# Sheet_MEZ.net
KiCad netlist of a schematic drawn in Altium Designer
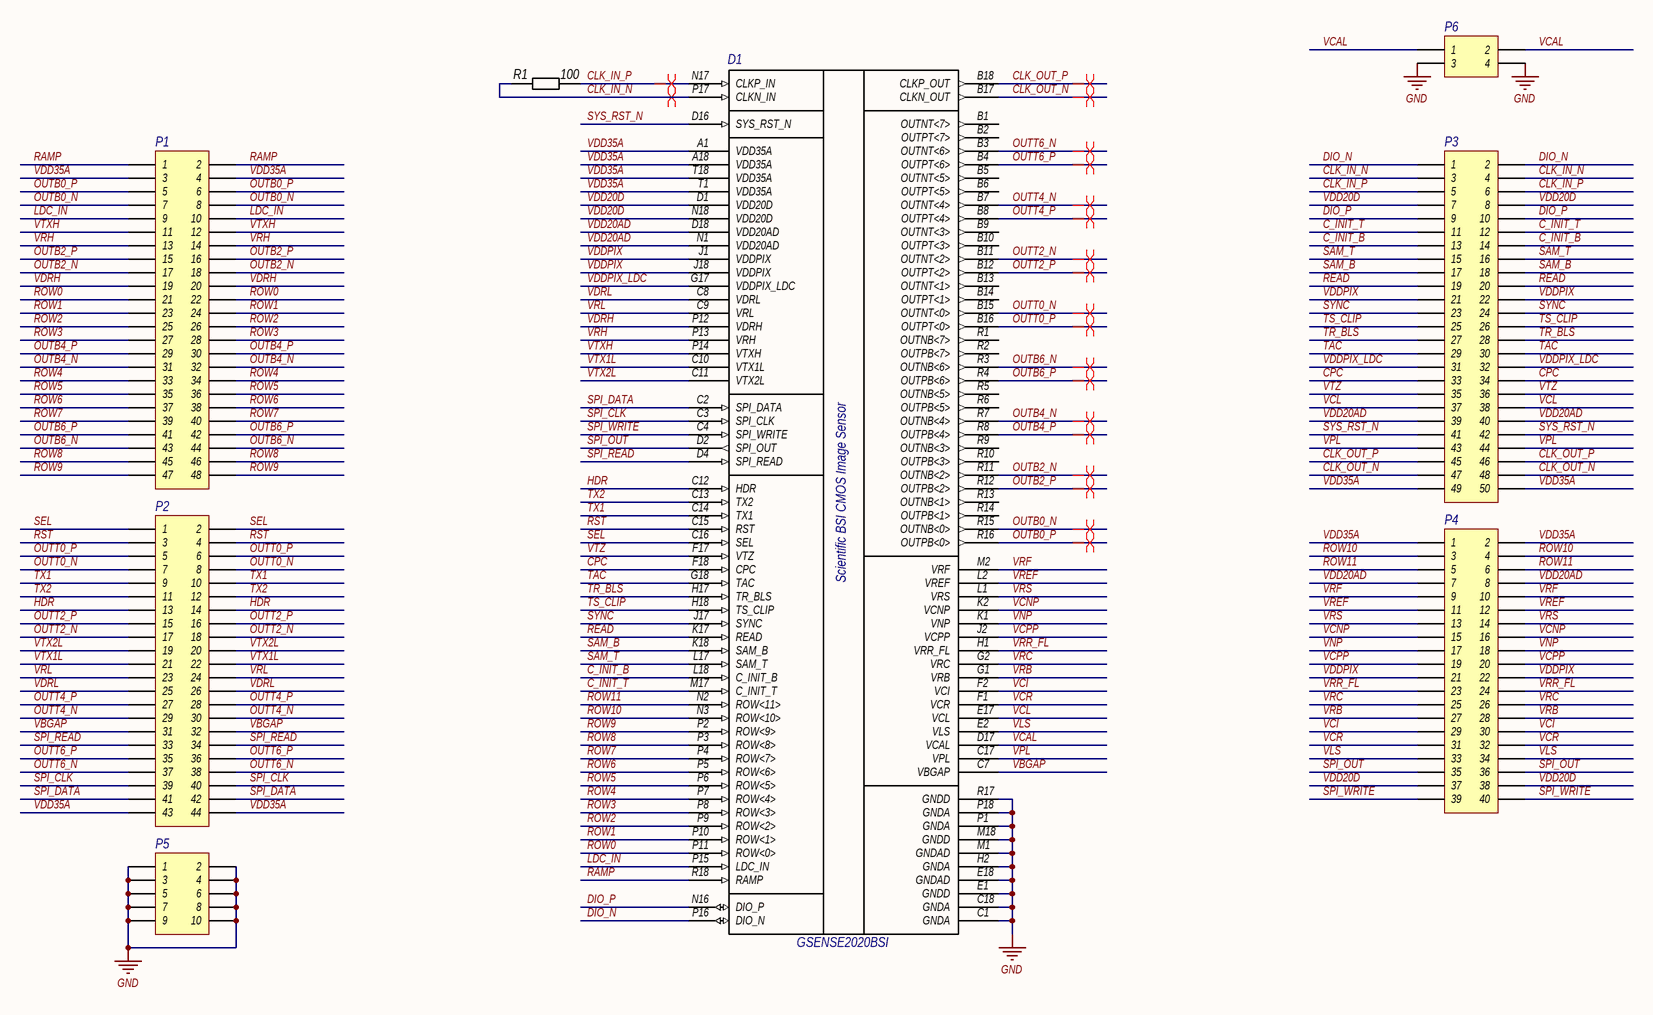
[diagram p0: Sheet_MEZ.SchDoc]

(export (version "E")
  (design (tool "Eeschema 10.0.6"))
  (components
    (comp (ref "D1")
      (value "GSENSE2020BSI")
      (footprint "GSENSE2020BSI")
      (libsource (lib "Schlib") (part "GSENSE2020BSI"))
    )
    (comp (ref "P1")
      (value "Header 24X2")
      (footprint "HDR2X24")
      (description "Header, 24-Pin, Dual row")
      (fields (field (name "PUBLISHER") "Altium Limited"))
      (libsource (lib "Miscellaneous Connectors") (part "Header 24X2"))
    )
    (comp (ref "P2")
      (value "Header 22X2")
      (footprint "HDR2X22")
      (description "Header, 22-Pin, Dual row")
      (fields (field (name "PUBLISHER") "Altium Limited"))
      (libsource (lib "Miscellaneous Connectors") (part "Header 22X2"))
    )
    (comp (ref "P3")
      (value "Header 25X2")
      (footprint "HDR2X25")
      (description "Header, 25-Pin, Dual row")
      (fields (field (name "PUBLISHER") "Altium Limited"))
      (libsource (lib "Miscellaneous Connectors") (part "Header 25X2"))
    )
    (comp (ref "P4")
      (value "Header 20X2")
      (footprint "HDR2X20")
      (description "Header, 20-Pin, Dual row")
      (fields (field (name "PUBLISHER") "Altium Limited"))
      (libsource (lib "Miscellaneous Connectors") (part "Header 20X2"))
    )
    (comp (ref "P5")
      (value "Header 5X2")
      (footprint "HDR2X5")
      (description "Header, 5-Pin, Dual row")
      (fields (field (name "PUBLISHER") "Altium Limited"))
      (libsource (lib "Miscellaneous Connectors") (part "Header 5X2"))
    )
    (comp (ref "P6")
      (value "Header 2X2")
      (footprint "HDR2X2")
      (description "Header, 2-Pin, Dual row")
      (fields (field (name "PUBLISHER") "Altium Limited"))
      (libsource (lib "Miscellaneous Connectors") (part "Header 2X2"))
    )
    (comp (ref "R1")
      (value "100")
      (footprint "RES")
      (description "Resistor")
      (libsource (lib "VPL") (part "Res"))
    )
  )
  (nets
    (net (code "1") (name "/CLK_IN_N") (class "Default")
      (node (ref "D1") (pin "P17") (pinfunction "CLKN_IN_P17") (pintype "input"))
      (node (ref "P3") (pin "3") (pinfunction "3_3") (pintype "passive"))
      (node (ref "P3") (pin "4") (pinfunction "4_4") (pintype "passive"))
      (node (ref "R1") (pin "1") (pintype "passive"))
    )
    (net (code "2") (name "/CLK_IN_P") (class "Default")
      (node (ref "D1") (pin "N17") (pinfunction "CLKP_IN_N17") (pintype "input"))
      (node (ref "P3") (pin "5") (pinfunction "5_5") (pintype "passive"))
      (node (ref "P3") (pin "6") (pinfunction "6_6") (pintype "passive"))
      (node (ref "R1") (pin "2") (pintype "passive"))
    )
    (net (code "3") (name "/CLK_OUT_N") (class "Default")
      (node (ref "D1") (pin "B17") (pinfunction "CLKN_OUT_B17") (pintype "output"))
      (node (ref "P3") (pin "47") (pinfunction "47_47") (pintype "passive"))
      (node (ref "P3") (pin "48") (pinfunction "48_48") (pintype "passive"))
    )
    (net (code "4") (name "/CLK_OUT_P") (class "Default")
      (node (ref "D1") (pin "B18") (pinfunction "CLKP_OUT_B18") (pintype "output"))
      (node (ref "P3") (pin "45") (pinfunction "45_45") (pintype "passive"))
      (node (ref "P3") (pin "46") (pinfunction "46_46") (pintype "passive"))
    )
    (net (code "5") (name "/CPC") (class "Default")
      (node (ref "D1") (pin "F18") (pinfunction "CPC_F18") (pintype "input"))
      (node (ref "P3") (pin "33") (pinfunction "33_33") (pintype "passive"))
      (node (ref "P3") (pin "34") (pinfunction "34_34") (pintype "passive"))
    )
    (net (code "6") (name "/C_INIT_B") (class "Default")
      (node (ref "D1") (pin "L18") (pinfunction "C_INIT_B_L18") (pintype "input"))
      (node (ref "P3") (pin "13") (pinfunction "13_13") (pintype "passive"))
      (node (ref "P3") (pin "14") (pinfunction "14_14") (pintype "passive"))
    )
    (net (code "7") (name "/C_INIT_T") (class "Default")
      (node (ref "D1") (pin "M17") (pinfunction "C_INIT_T_M17") (pintype "input"))
      (node (ref "P3") (pin "11") (pinfunction "11_11") (pintype "passive"))
      (node (ref "P3") (pin "12") (pinfunction "12_12") (pintype "passive"))
    )
    (net (code "8") (name "/DIO_N") (class "Default")
      (node (ref "D1") (pin "P16") (pinfunction "DIO_N_P16") (pintype "bidirectional"))
      (node (ref "P3") (pin "1") (pinfunction "1_1") (pintype "passive"))
      (node (ref "P3") (pin "2") (pinfunction "2_2") (pintype "passive"))
    )
    (net (code "9") (name "/DIO_P") (class "Default")
      (node (ref "D1") (pin "N16") (pinfunction "DIO_P_N16") (pintype "bidirectional"))
      (node (ref "P3") (pin "10") (pinfunction "10_10") (pintype "passive"))
      (node (ref "P3") (pin "9") (pinfunction "9_9") (pintype "passive"))
    )
    (net (code "10") (name "/HDR") (class "Default")
      (node (ref "D1") (pin "C12") (pinfunction "HDR_C12") (pintype "input"))
      (node (ref "P2") (pin "13") (pinfunction "13_13") (pintype "passive"))
      (node (ref "P2") (pin "14") (pinfunction "14_14") (pintype "passive"))
    )
    (net (code "11") (name "/LDC_IN") (class "Default")
      (node (ref "D1") (pin "P15") (pinfunction "LDC_IN_P15") (pintype "input"))
      (node (ref "P1") (pin "10") (pinfunction "10_10") (pintype "passive"))
      (node (ref "P1") (pin "9") (pinfunction "9_9") (pintype "passive"))
    )
    (net (code "12") (name "/OUTB0_N") (class "Default")
      (node (ref "D1") (pin "R15") (pinfunction "OUTNB<0>_R15") (pintype "output"))
      (node (ref "P1") (pin "7") (pinfunction "7_7") (pintype "passive"))
      (node (ref "P1") (pin "8") (pinfunction "8_8") (pintype "passive"))
    )
    (net (code "13") (name "/OUTB0_P") (class "Default")
      (node (ref "D1") (pin "R16") (pinfunction "OUTPB<0>_R16") (pintype "output"))
      (node (ref "P1") (pin "5") (pinfunction "5_5") (pintype "passive"))
      (node (ref "P1") (pin "6") (pinfunction "6_6") (pintype "passive"))
    )
    (net (code "14") (name "/OUTB2_N") (class "Default")
      (node (ref "D1") (pin "R11") (pinfunction "OUTNB<2>_R11") (pintype "output"))
      (node (ref "P1") (pin "17") (pinfunction "17_17") (pintype "passive"))
      (node (ref "P1") (pin "18") (pinfunction "18_18") (pintype "passive"))
    )
    (net (code "15") (name "/OUTB2_P") (class "Default")
      (node (ref "D1") (pin "R12") (pinfunction "OUTPB<2>_R12") (pintype "output"))
      (node (ref "P1") (pin "15") (pinfunction "15_15") (pintype "passive"))
      (node (ref "P1") (pin "16") (pinfunction "16_16") (pintype "passive"))
    )
    (net (code "16") (name "/OUTB4_N") (class "Default")
      (node (ref "D1") (pin "R7") (pinfunction "OUTNB<4>_R7") (pintype "output"))
      (node (ref "P1") (pin "31") (pinfunction "31_31") (pintype "passive"))
      (node (ref "P1") (pin "32") (pinfunction "32_32") (pintype "passive"))
    )
    (net (code "17") (name "/OUTB4_P") (class "Default")
      (node (ref "D1") (pin "R8") (pinfunction "OUTPB<4>_R8") (pintype "output"))
      (node (ref "P1") (pin "29") (pinfunction "29_29") (pintype "passive"))
      (node (ref "P1") (pin "30") (pinfunction "30_30") (pintype "passive"))
    )
    (net (code "18") (name "/OUTB6_N") (class "Default")
      (node (ref "D1") (pin "R3") (pinfunction "OUTNB<6>_R3") (pintype "output"))
      (node (ref "P1") (pin "43") (pinfunction "43_43") (pintype "passive"))
      (node (ref "P1") (pin "44") (pinfunction "44_44") (pintype "passive"))
    )
    (net (code "19") (name "/OUTB6_P") (class "Default")
      (node (ref "D1") (pin "R4") (pinfunction "OUTPB<6>_R4") (pintype "output"))
      (node (ref "P1") (pin "41") (pinfunction "41_41") (pintype "passive"))
      (node (ref "P1") (pin "42") (pinfunction "42_42") (pintype "passive"))
    )
    (net (code "20") (name "/OUTT0_N") (class "Default")
      (node (ref "D1") (pin "B15") (pinfunction "OUTNT<0>_B15") (pintype "output"))
      (node (ref "P2") (pin "7") (pinfunction "7_7") (pintype "passive"))
      (node (ref "P2") (pin "8") (pinfunction "8_8") (pintype "passive"))
    )
    (net (code "21") (name "/OUTT0_P") (class "Default")
      (node (ref "D1") (pin "B16") (pinfunction "OUTPT<0>_B16") (pintype "output"))
      (node (ref "P2") (pin "5") (pinfunction "5_5") (pintype "passive"))
      (node (ref "P2") (pin "6") (pinfunction "6_6") (pintype "passive"))
    )
    (net (code "22") (name "/OUTT2_N") (class "Default")
      (node (ref "D1") (pin "B11") (pinfunction "OUTNT<2>_B11") (pintype "output"))
      (node (ref "P2") (pin "17") (pinfunction "17_17") (pintype "passive"))
      (node (ref "P2") (pin "18") (pinfunction "18_18") (pintype "passive"))
    )
    (net (code "23") (name "/OUTT2_P") (class "Default")
      (node (ref "D1") (pin "B12") (pinfunction "OUTPT<2>_B12") (pintype "output"))
      (node (ref "P2") (pin "15") (pinfunction "15_15") (pintype "passive"))
      (node (ref "P2") (pin "16") (pinfunction "16_16") (pintype "passive"))
    )
    (net (code "24") (name "/OUTT4_N") (class "Default")
      (node (ref "D1") (pin "B7") (pinfunction "OUTNT<4>_B7") (pintype "output"))
      (node (ref "P2") (pin "29") (pinfunction "29_29") (pintype "passive"))
      (node (ref "P2") (pin "30") (pinfunction "30_30") (pintype "passive"))
    )
    (net (code "25") (name "/OUTT4_P") (class "Default")
      (node (ref "D1") (pin "B8") (pinfunction "OUTPT<4>_B8") (pintype "output"))
      (node (ref "P2") (pin "27") (pinfunction "27_27") (pintype "passive"))
      (node (ref "P2") (pin "28") (pinfunction "28_28") (pintype "passive"))
    )
    (net (code "26") (name "/OUTT6_N") (class "Default")
      (node (ref "D1") (pin "B3") (pinfunction "OUTNT<6>_B3") (pintype "output"))
      (node (ref "P2") (pin "37") (pinfunction "37_37") (pintype "passive"))
      (node (ref "P2") (pin "38") (pinfunction "38_38") (pintype "passive"))
    )
    (net (code "27") (name "/OUTT6_P") (class "Default")
      (node (ref "D1") (pin "B4") (pinfunction "OUTPT<6>_B4") (pintype "output"))
      (node (ref "P2") (pin "35") (pinfunction "35_35") (pintype "passive"))
      (node (ref "P2") (pin "36") (pinfunction "36_36") (pintype "passive"))
    )
    (net (code "28") (name "/RAMP") (class "Default")
      (node (ref "D1") (pin "R18") (pinfunction "RAMP_R18") (pintype "input"))
      (node (ref "P1") (pin "1") (pinfunction "1_1") (pintype "passive"))
      (node (ref "P1") (pin "2") (pinfunction "2_2") (pintype "passive"))
    )
    (net (code "29") (name "/READ") (class "Default")
      (node (ref "D1") (pin "K17") (pinfunction "READ_K17") (pintype "input"))
      (node (ref "P3") (pin "19") (pinfunction "19_19") (pintype "passive"))
      (node (ref "P3") (pin "20") (pinfunction "20_20") (pintype "passive"))
    )
    (net (code "30") (name "/ROW0") (class "Default")
      (node (ref "D1") (pin "P11") (pinfunction "ROW<0>_P11") (pintype "input"))
      (node (ref "P1") (pin "21") (pinfunction "21_21") (pintype "passive"))
      (node (ref "P1") (pin "22") (pinfunction "22_22") (pintype "passive"))
    )
    (net (code "31") (name "/ROW1") (class "Default")
      (node (ref "D1") (pin "P10") (pinfunction "ROW<1>_P10") (pintype "input"))
      (node (ref "P1") (pin "23") (pinfunction "23_23") (pintype "passive"))
      (node (ref "P1") (pin "24") (pinfunction "24_24") (pintype "passive"))
    )
    (net (code "32") (name "/ROW2") (class "Default")
      (node (ref "D1") (pin "P9") (pinfunction "ROW<2>_P9") (pintype "input"))
      (node (ref "P1") (pin "25") (pinfunction "25_25") (pintype "passive"))
      (node (ref "P1") (pin "26") (pinfunction "26_26") (pintype "passive"))
    )
    (net (code "33") (name "/ROW3") (class "Default")
      (node (ref "D1") (pin "P8") (pinfunction "ROW<3>_P8") (pintype "input"))
      (node (ref "P1") (pin "27") (pinfunction "27_27") (pintype "passive"))
      (node (ref "P1") (pin "28") (pinfunction "28_28") (pintype "passive"))
    )
    (net (code "34") (name "/ROW4") (class "Default")
      (node (ref "D1") (pin "P7") (pinfunction "ROW<4>_P7") (pintype "input"))
      (node (ref "P1") (pin "33") (pinfunction "33_33") (pintype "passive"))
      (node (ref "P1") (pin "34") (pinfunction "34_34") (pintype "passive"))
    )
    (net (code "35") (name "/ROW5") (class "Default")
      (node (ref "D1") (pin "P6") (pinfunction "ROW<5>_P6") (pintype "input"))
      (node (ref "P1") (pin "35") (pinfunction "35_35") (pintype "passive"))
      (node (ref "P1") (pin "36") (pinfunction "36_36") (pintype "passive"))
    )
    (net (code "36") (name "/ROW6") (class "Default")
      (node (ref "D1") (pin "P5") (pinfunction "ROW<6>_P5") (pintype "input"))
      (node (ref "P1") (pin "37") (pinfunction "37_37") (pintype "passive"))
      (node (ref "P1") (pin "38") (pinfunction "38_38") (pintype "passive"))
    )
    (net (code "37") (name "/ROW7") (class "Default")
      (node (ref "D1") (pin "P4") (pinfunction "ROW<7>_P4") (pintype "input"))
      (node (ref "P1") (pin "39") (pinfunction "39_39") (pintype "passive"))
      (node (ref "P1") (pin "40") (pinfunction "40_40") (pintype "passive"))
    )
    (net (code "38") (name "/ROW8") (class "Default")
      (node (ref "D1") (pin "P3") (pinfunction "ROW<8>_P3") (pintype "input"))
      (node (ref "P1") (pin "45") (pinfunction "45_45") (pintype "passive"))
      (node (ref "P1") (pin "46") (pinfunction "46_46") (pintype "passive"))
    )
    (net (code "39") (name "/ROW9") (class "Default")
      (node (ref "D1") (pin "P2") (pinfunction "ROW<9>_P2") (pintype "input"))
      (node (ref "P1") (pin "47") (pinfunction "47_47") (pintype "passive"))
      (node (ref "P1") (pin "48") (pinfunction "48_48") (pintype "passive"))
    )
    (net (code "40") (name "/ROW10") (class "Default")
      (node (ref "D1") (pin "N3") (pinfunction "ROW<10>_N3") (pintype "input"))
      (node (ref "P4") (pin "3") (pinfunction "3_3") (pintype "passive"))
      (node (ref "P4") (pin "4") (pinfunction "4_4") (pintype "passive"))
    )
    (net (code "41") (name "/ROW11") (class "Default")
      (node (ref "D1") (pin "N2") (pinfunction "ROW<11>_N2") (pintype "input"))
      (node (ref "P4") (pin "5") (pinfunction "5_5") (pintype "passive"))
      (node (ref "P4") (pin "6") (pinfunction "6_6") (pintype "passive"))
    )
    (net (code "42") (name "/RST") (class "Default")
      (node (ref "D1") (pin "C15") (pinfunction "RST_C15") (pintype "input"))
      (node (ref "P2") (pin "3") (pinfunction "3_3") (pintype "passive"))
      (node (ref "P2") (pin "4") (pinfunction "4_4") (pintype "passive"))
    )
    (net (code "43") (name "/SAM_B") (class "Default")
      (node (ref "D1") (pin "K18") (pinfunction "SAM_B_K18") (pintype "input"))
      (node (ref "P3") (pin "17") (pinfunction "17_17") (pintype "passive"))
      (node (ref "P3") (pin "18") (pinfunction "18_18") (pintype "passive"))
    )
    (net (code "44") (name "/SAM_T") (class "Default")
      (node (ref "D1") (pin "L17") (pinfunction "SAM_T_L17") (pintype "input"))
      (node (ref "P3") (pin "15") (pinfunction "15_15") (pintype "passive"))
      (node (ref "P3") (pin "16") (pinfunction "16_16") (pintype "passive"))
    )
    (net (code "45") (name "/SEL") (class "Default")
      (node (ref "D1") (pin "C16") (pinfunction "SEL_C16") (pintype "input"))
      (node (ref "P2") (pin "1") (pinfunction "1_1") (pintype "passive"))
      (node (ref "P2") (pin "2") (pinfunction "2_2") (pintype "passive"))
    )
    (net (code "46") (name "/SPI_CLK") (class "Default")
      (node (ref "D1") (pin "C3") (pinfunction "SPI_CLK_C3") (pintype "input"))
      (node (ref "P2") (pin "39") (pinfunction "39_39") (pintype "passive"))
      (node (ref "P2") (pin "40") (pinfunction "40_40") (pintype "passive"))
    )
    (net (code "47") (name "/SPI_DATA") (class "Default")
      (node (ref "D1") (pin "C2") (pinfunction "SPI_DATA_C2") (pintype "input"))
      (node (ref "P2") (pin "41") (pinfunction "41_41") (pintype "passive"))
      (node (ref "P2") (pin "42") (pinfunction "42_42") (pintype "passive"))
    )
    (net (code "48") (name "/SPI_OUT") (class "Default")
      (node (ref "D1") (pin "D2") (pinfunction "SPI_OUT_D2") (pintype "output"))
      (node (ref "P4") (pin "35") (pinfunction "35_35") (pintype "passive"))
      (node (ref "P4") (pin "36") (pinfunction "36_36") (pintype "passive"))
    )
    (net (code "49") (name "/SPI_READ") (class "Default")
      (node (ref "D1") (pin "D4") (pinfunction "SPI_READ_D4") (pintype "input"))
      (node (ref "P2") (pin "33") (pinfunction "33_33") (pintype "passive"))
      (node (ref "P2") (pin "34") (pinfunction "34_34") (pintype "passive"))
    )
    (net (code "50") (name "/SPI_WRITE") (class "Default")
      (node (ref "D1") (pin "C4") (pinfunction "SPI_WRITE_C4") (pintype "input"))
      (node (ref "P4") (pin "39") (pinfunction "39_39") (pintype "passive"))
      (node (ref "P4") (pin "40") (pinfunction "40_40") (pintype "passive"))
    )
    (net (code "51") (name "/SYNC") (class "Default")
      (node (ref "D1") (pin "J17") (pinfunction "SYNC_J17") (pintype "input"))
      (node (ref "P3") (pin "23") (pinfunction "23_23") (pintype "passive"))
      (node (ref "P3") (pin "24") (pinfunction "24_24") (pintype "passive"))
    )
    (net (code "52") (name "/SYS_RST_N") (class "Default")
      (node (ref "D1") (pin "D16") (pinfunction "SYS_RST_N_D16") (pintype "input"))
      (node (ref "P3") (pin "41") (pinfunction "41_41") (pintype "passive"))
      (node (ref "P3") (pin "42") (pinfunction "42_42") (pintype "passive"))
    )
    (net (code "53") (name "/TAC") (class "Default")
      (node (ref "D1") (pin "G18") (pinfunction "TAC_G18") (pintype "input"))
      (node (ref "P3") (pin "29") (pinfunction "29_29") (pintype "passive"))
      (node (ref "P3") (pin "30") (pinfunction "30_30") (pintype "passive"))
    )
    (net (code "54") (name "/TR_BLS") (class "Default")
      (node (ref "D1") (pin "H17") (pinfunction "TR_BLS_H17") (pintype "input"))
      (node (ref "P3") (pin "27") (pinfunction "27_27") (pintype "passive"))
      (node (ref "P3") (pin "28") (pinfunction "28_28") (pintype "passive"))
    )
    (net (code "55") (name "/TS_CLIP") (class "Default")
      (node (ref "D1") (pin "H18") (pinfunction "TS_CLIP_H18") (pintype "input"))
      (node (ref "P3") (pin "25") (pinfunction "25_25") (pintype "passive"))
      (node (ref "P3") (pin "26") (pinfunction "26_26") (pintype "passive"))
    )
    (net (code "56") (name "/TX1") (class "Default")
      (node (ref "D1") (pin "C14") (pinfunction "TX1_C14") (pintype "input"))
      (node (ref "P2") (pin "10") (pinfunction "10_10") (pintype "passive"))
      (node (ref "P2") (pin "9") (pinfunction "9_9") (pintype "passive"))
    )
    (net (code "57") (name "/TX2") (class "Default")
      (node (ref "D1") (pin "C13") (pinfunction "TX2_C13") (pintype "input"))
      (node (ref "P2") (pin "11") (pinfunction "11_11") (pintype "passive"))
      (node (ref "P2") (pin "12") (pinfunction "12_12") (pintype "passive"))
    )
    (net (code "58") (name "/VBGAP") (class "Default")
      (node (ref "D1") (pin "C7") (pinfunction "VBGAP_C7") (pintype "passive"))
      (node (ref "P2") (pin "31") (pinfunction "31_31") (pintype "passive"))
      (node (ref "P2") (pin "32") (pinfunction "32_32") (pintype "passive"))
    )
    (net (code "59") (name "/VCAL") (class "Default")
      (node (ref "D1") (pin "D17") (pinfunction "VCAL_D17") (pintype "passive"))
      (node (ref "P6") (pin "1") (pinfunction "1_1") (pintype "passive"))
      (node (ref "P6") (pin "2") (pinfunction "2_2") (pintype "passive"))
    )
    (net (code "60") (name "/VCI") (class "Default")
      (node (ref "D1") (pin "F2") (pinfunction "VCI_F2") (pintype "passive"))
      (node (ref "P4") (pin "29") (pinfunction "29_29") (pintype "passive"))
      (node (ref "P4") (pin "30") (pinfunction "30_30") (pintype "passive"))
    )
    (net (code "61") (name "/VCL") (class "Default")
      (node (ref "D1") (pin "E17") (pinfunction "VCL_E17") (pintype "passive"))
      (node (ref "P3") (pin "37") (pinfunction "37_37") (pintype "passive"))
      (node (ref "P3") (pin "38") (pinfunction "38_38") (pintype "passive"))
    )
    (net (code "62") (name "/VCNP") (class "Default")
      (node (ref "D1") (pin "K2") (pinfunction "VCNP_K2") (pintype "passive"))
      (node (ref "P4") (pin "15") (pinfunction "15_15") (pintype "passive"))
      (node (ref "P4") (pin "16") (pinfunction "16_16") (pintype "passive"))
    )
    (net (code "63") (name "/VCPP") (class "Default")
      (node (ref "D1") (pin "J2") (pinfunction "VCPP_J2") (pintype "passive"))
      (node (ref "P4") (pin "19") (pinfunction "19_19") (pintype "passive"))
      (node (ref "P4") (pin "20") (pinfunction "20_20") (pintype "passive"))
    )
    (net (code "64") (name "/VCR") (class "Default")
      (node (ref "D1") (pin "F1") (pinfunction "VCR_F1") (pintype "passive"))
      (node (ref "P4") (pin "31") (pinfunction "31_31") (pintype "passive"))
      (node (ref "P4") (pin "32") (pinfunction "32_32") (pintype "passive"))
    )
    (net (code "65") (name "/VDD20AD") (class "Default")
      (node (ref "D1") (pin "D18") (pinfunction "VDD20AD_D18") (pintype "passive"))
      (node (ref "D1") (pin "N1") (pinfunction "VDD20AD_N1") (pintype "passive"))
      (node (ref "P3") (pin "39") (pinfunction "39_39") (pintype "passive"))
      (node (ref "P3") (pin "40") (pinfunction "40_40") (pintype "passive"))
      (node (ref "P4") (pin "7") (pinfunction "7_7") (pintype "passive"))
      (node (ref "P4") (pin "8") (pinfunction "8_8") (pintype "passive"))
    )
    (net (code "66") (name "/VDD20D") (class "Default")
      (node (ref "D1") (pin "D1") (pinfunction "VDD20D_D1") (pintype "passive"))
      (node (ref "D1") (pin "N18") (pinfunction "VDD20D_N18") (pintype "passive"))
      (node (ref "P3") (pin "7") (pinfunction "7_7") (pintype "passive"))
      (node (ref "P3") (pin "8") (pinfunction "8_8") (pintype "passive"))
      (node (ref "P4") (pin "37") (pinfunction "37_37") (pintype "passive"))
      (node (ref "P4") (pin "38") (pinfunction "38_38") (pintype "passive"))
    )
    (net (code "67") (name "/VDD35A") (class "Default")
      (node (ref "D1") (pin "A1") (pinfunction "VDD35A_A1") (pintype "passive"))
      (node (ref "D1") (pin "A18") (pinfunction "VDD35A_A18") (pintype "passive"))
      (node (ref "D1") (pin "T1") (pinfunction "VDD35A_T1") (pintype "passive"))
      (node (ref "D1") (pin "T18") (pinfunction "VDD35A_T18") (pintype "passive"))
      (node (ref "P1") (pin "3") (pinfunction "3_3") (pintype "passive"))
      (node (ref "P1") (pin "4") (pinfunction "4_4") (pintype "passive"))
      (node (ref "P2") (pin "43") (pinfunction "43_43") (pintype "passive"))
      (node (ref "P2") (pin "44") (pinfunction "44_44") (pintype "passive"))
      (node (ref "P3") (pin "49") (pinfunction "49_49") (pintype "passive"))
      (node (ref "P3") (pin "50") (pinfunction "50_50") (pintype "passive"))
      (node (ref "P4") (pin "1") (pinfunction "1_1") (pintype "passive"))
      (node (ref "P4") (pin "2") (pinfunction "2_2") (pintype "passive"))
    )
    (net (code "68") (name "/VDDPIX") (class "Default")
      (node (ref "D1") (pin "J1") (pinfunction "VDDPIX_J1") (pintype "passive"))
      (node (ref "D1") (pin "J18") (pinfunction "VDDPIX_J18") (pintype "passive"))
      (node (ref "P3") (pin "21") (pinfunction "21_21") (pintype "passive"))
      (node (ref "P3") (pin "22") (pinfunction "22_22") (pintype "passive"))
      (node (ref "P4") (pin "21") (pinfunction "21_21") (pintype "passive"))
      (node (ref "P4") (pin "22") (pinfunction "22_22") (pintype "passive"))
    )
    (net (code "69") (name "/VDDPIX_LDC") (class "Default")
      (node (ref "D1") (pin "G17") (pinfunction "VDDPIX_LDC_G17") (pintype "passive"))
      (node (ref "P3") (pin "31") (pinfunction "31_31") (pintype "passive"))
      (node (ref "P3") (pin "32") (pinfunction "32_32") (pintype "passive"))
    )
    (net (code "70") (name "/VDRH") (class "Default")
      (node (ref "D1") (pin "P12") (pinfunction "VDRH_P12") (pintype "passive"))
      (node (ref "P1") (pin "19") (pinfunction "19_19") (pintype "passive"))
      (node (ref "P1") (pin "20") (pinfunction "20_20") (pintype "passive"))
    )
    (net (code "71") (name "/VDRL") (class "Default")
      (node (ref "D1") (pin "C8") (pinfunction "VDRL_C8") (pintype "passive"))
      (node (ref "P2") (pin "25") (pinfunction "25_25") (pintype "passive"))
      (node (ref "P2") (pin "26") (pinfunction "26_26") (pintype "passive"))
    )
    (net (code "72") (name "/VLS") (class "Default")
      (node (ref "D1") (pin "E2") (pinfunction "VLS_E2") (pintype "passive"))
      (node (ref "P4") (pin "33") (pinfunction "33_33") (pintype "passive"))
      (node (ref "P4") (pin "34") (pinfunction "34_34") (pintype "passive"))
    )
    (net (code "73") (name "/VNP") (class "Default")
      (node (ref "D1") (pin "K1") (pinfunction "VNP_K1") (pintype "passive"))
      (node (ref "P4") (pin "17") (pinfunction "17_17") (pintype "passive"))
      (node (ref "P4") (pin "18") (pinfunction "18_18") (pintype "passive"))
    )
    (net (code "74") (name "/VPL") (class "Default")
      (node (ref "D1") (pin "C17") (pinfunction "VPL_C17") (pintype "passive"))
      (node (ref "P3") (pin "43") (pinfunction "43_43") (pintype "passive"))
      (node (ref "P3") (pin "44") (pinfunction "44_44") (pintype "passive"))
    )
    (net (code "75") (name "/VRB") (class "Default")
      (node (ref "D1") (pin "G1") (pinfunction "VRB_G1") (pintype "passive"))
      (node (ref "P4") (pin "27") (pinfunction "27_27") (pintype "passive"))
      (node (ref "P4") (pin "28") (pinfunction "28_28") (pintype "passive"))
    )
    (net (code "76") (name "/VRC") (class "Default")
      (node (ref "D1") (pin "G2") (pinfunction "VRC_G2") (pintype "passive"))
      (node (ref "P4") (pin "25") (pinfunction "25_25") (pintype "passive"))
      (node (ref "P4") (pin "26") (pinfunction "26_26") (pintype "passive"))
    )
    (net (code "77") (name "/VREF") (class "Default")
      (node (ref "D1") (pin "L2") (pinfunction "VREF_L2") (pintype "passive"))
      (node (ref "P4") (pin "11") (pinfunction "11_11") (pintype "passive"))
      (node (ref "P4") (pin "12") (pinfunction "12_12") (pintype "passive"))
    )
    (net (code "78") (name "/VRF") (class "Default")
      (node (ref "D1") (pin "M2") (pinfunction "VRF_M2") (pintype "passive"))
      (node (ref "P4") (pin "10") (pinfunction "10_10") (pintype "passive"))
      (node (ref "P4") (pin "9") (pinfunction "9_9") (pintype "passive"))
    )
    (net (code "79") (name "/VRH") (class "Default")
      (node (ref "D1") (pin "P13") (pinfunction "VRH_P13") (pintype "passive"))
      (node (ref "P1") (pin "13") (pinfunction "13_13") (pintype "passive"))
      (node (ref "P1") (pin "14") (pinfunction "14_14") (pintype "passive"))
    )
    (net (code "80") (name "/VRL") (class "Default")
      (node (ref "D1") (pin "C9") (pinfunction "VRL_C9") (pintype "passive"))
      (node (ref "P2") (pin "23") (pinfunction "23_23") (pintype "passive"))
      (node (ref "P2") (pin "24") (pinfunction "24_24") (pintype "passive"))
    )
    (net (code "81") (name "/VRR_FL") (class "Default")
      (node (ref "D1") (pin "H1") (pinfunction "VRR_FL_H1") (pintype "passive"))
      (node (ref "P4") (pin "23") (pinfunction "23_23") (pintype "passive"))
      (node (ref "P4") (pin "24") (pinfunction "24_24") (pintype "passive"))
    )
    (net (code "82") (name "/VRS") (class "Default")
      (node (ref "D1") (pin "L1") (pinfunction "VRS_L1") (pintype "passive"))
      (node (ref "P4") (pin "13") (pinfunction "13_13") (pintype "passive"))
      (node (ref "P4") (pin "14") (pinfunction "14_14") (pintype "passive"))
    )
    (net (code "83") (name "/VTX1L") (class "Default")
      (node (ref "D1") (pin "C10") (pinfunction "VTX1L_C10") (pintype "passive"))
      (node (ref "P2") (pin "21") (pinfunction "21_21") (pintype "passive"))
      (node (ref "P2") (pin "22") (pinfunction "22_22") (pintype "passive"))
    )
    (net (code "84") (name "/VTX2L") (class "Default")
      (node (ref "D1") (pin "C11") (pinfunction "VTX2L_C11") (pintype "passive"))
      (node (ref "P2") (pin "19") (pinfunction "19_19") (pintype "passive"))
      (node (ref "P2") (pin "20") (pinfunction "20_20") (pintype "passive"))
    )
    (net (code "85") (name "/VTXH") (class "Default")
      (node (ref "D1") (pin "P14") (pinfunction "VTXH_P14") (pintype "passive"))
      (node (ref "P1") (pin "11") (pinfunction "11_11") (pintype "passive"))
      (node (ref "P1") (pin "12") (pinfunction "12_12") (pintype "passive"))
    )
    (net (code "86") (name "/VTZ") (class "Default")
      (node (ref "D1") (pin "F17") (pinfunction "VTZ_F17") (pintype "input"))
      (node (ref "P3") (pin "35") (pinfunction "35_35") (pintype "passive"))
      (node (ref "P3") (pin "36") (pinfunction "36_36") (pintype "passive"))
    )
    (net (code "87") (name "GND") (class "Default")
      (node (ref "D1") (pin "C1") (pinfunction "GNDA_C1") (pintype "passive"))
      (node (ref "D1") (pin "C18") (pinfunction "GNDA_C18") (pintype "passive"))
      (node (ref "D1") (pin "E1") (pinfunction "GNDD_E1") (pintype "passive"))
      (node (ref "D1") (pin "E18") (pinfunction "GNDAD_E18") (pintype "passive"))
      (node (ref "D1") (pin "H2") (pinfunction "GNDA_H2") (pintype "passive"))
      (node (ref "D1") (pin "M1") (pinfunction "GNDAD_M1") (pintype "passive"))
      (node (ref "D1") (pin "M18") (pinfunction "GNDD_M18") (pintype "passive"))
      (node (ref "D1") (pin "P1") (pinfunction "GNDA_P1") (pintype "passive"))
      (node (ref "D1") (pin "P18") (pinfunction "GNDA_P18") (pintype "passive"))
      (node (ref "D1") (pin "R17") (pinfunction "GNDD_R17") (pintype "passive"))
      (node (ref "P5") (pin "1") (pinfunction "1_1") (pintype "passive"))
      (node (ref "P5") (pin "10") (pinfunction "10_10") (pintype "passive"))
      (node (ref "P5") (pin "2") (pinfunction "2_2") (pintype "passive"))
      (node (ref "P5") (pin "3") (pinfunction "3_3") (pintype "passive"))
      (node (ref "P5") (pin "4") (pinfunction "4_4") (pintype "passive"))
      (node (ref "P5") (pin "5") (pinfunction "5_5") (pintype "passive"))
      (node (ref "P5") (pin "6") (pinfunction "6_6") (pintype "passive"))
      (node (ref "P5") (pin "7") (pinfunction "7_7") (pintype "passive"))
      (node (ref "P5") (pin "8") (pinfunction "8_8") (pintype "passive"))
      (node (ref "P5") (pin "9") (pinfunction "9_9") (pintype "passive"))
      (node (ref "P6") (pin "3") (pinfunction "3_3") (pintype "passive"))
      (node (ref "P6") (pin "4") (pinfunction "4_4") (pintype "passive"))
    )
    (net (code "88") (name "unconnected-(D1-OUTNB<1>-PadR13)") (class "Default")
      (node (ref "D1") (pin "R13") (pinfunction "OUTNB<1>_R13") (pintype "output"))
    )
    (net (code "89") (name "unconnected-(D1-OUTNB<3>-PadR9)") (class "Default")
      (node (ref "D1") (pin "R9") (pinfunction "OUTNB<3>_R9") (pintype "output"))
    )
    (net (code "90") (name "unconnected-(D1-OUTNB<5>-PadR5)") (class "Default")
      (node (ref "D1") (pin "R5") (pinfunction "OUTNB<5>_R5") (pintype "output"))
    )
    (net (code "91") (name "unconnected-(D1-OUTNB<7>-PadR1)") (class "Default")
      (node (ref "D1") (pin "R1") (pinfunction "OUTNB<7>_R1") (pintype "output"))
    )
    (net (code "92") (name "unconnected-(D1-OUTNT<1>-PadB13)") (class "Default")
      (node (ref "D1") (pin "B13") (pinfunction "OUTNT<1>_B13") (pintype "output"))
    )
    (net (code "93") (name "unconnected-(D1-OUTNT<3>-PadB9)") (class "Default")
      (node (ref "D1") (pin "B9") (pinfunction "OUTNT<3>_B9") (pintype "output"))
    )
    (net (code "94") (name "unconnected-(D1-OUTNT<5>-PadB5)") (class "Default")
      (node (ref "D1") (pin "B5") (pinfunction "OUTNT<5>_B5") (pintype "output"))
    )
    (net (code "95") (name "unconnected-(D1-OUTNT<7>-PadB1)") (class "Default")
      (node (ref "D1") (pin "B1") (pinfunction "OUTNT<7>_B1") (pintype "output"))
    )
    (net (code "96") (name "unconnected-(D1-OUTPB<1>-PadR14)") (class "Default")
      (node (ref "D1") (pin "R14") (pinfunction "OUTPB<1>_R14") (pintype "output"))
    )
    (net (code "97") (name "unconnected-(D1-OUTPB<3>-PadR10)") (class "Default")
      (node (ref "D1") (pin "R10") (pinfunction "OUTPB<3>_R10") (pintype "output"))
    )
    (net (code "98") (name "unconnected-(D1-OUTPB<5>-PadR6)") (class "Default")
      (node (ref "D1") (pin "R6") (pinfunction "OUTPB<5>_R6") (pintype "output"))
    )
    (net (code "99") (name "unconnected-(D1-OUTPB<7>-PadR2)") (class "Default")
      (node (ref "D1") (pin "R2") (pinfunction "OUTPB<7>_R2") (pintype "output"))
    )
    (net (code "100") (name "unconnected-(D1-OUTPT<1>-PadB14)") (class "Default")
      (node (ref "D1") (pin "B14") (pinfunction "OUTPT<1>_B14") (pintype "output"))
    )
    (net (code "101") (name "unconnected-(D1-OUTPT<3>-PadB10)") (class "Default")
      (node (ref "D1") (pin "B10") (pinfunction "OUTPT<3>_B10") (pintype "output"))
    )
    (net (code "102") (name "unconnected-(D1-OUTPT<5>-PadB6)") (class "Default")
      (node (ref "D1") (pin "B6") (pinfunction "OUTPT<5>_B6") (pintype "output"))
    )
    (net (code "103") (name "unconnected-(D1-OUTPT<7>-PadB2)") (class "Default")
      (node (ref "D1") (pin "B2") (pinfunction "OUTPT<7>_B2") (pintype "output"))
    )
  )
)
